# NSSTC-BAK.net
KiCad netlist of a schematic drawn in Altium Designer
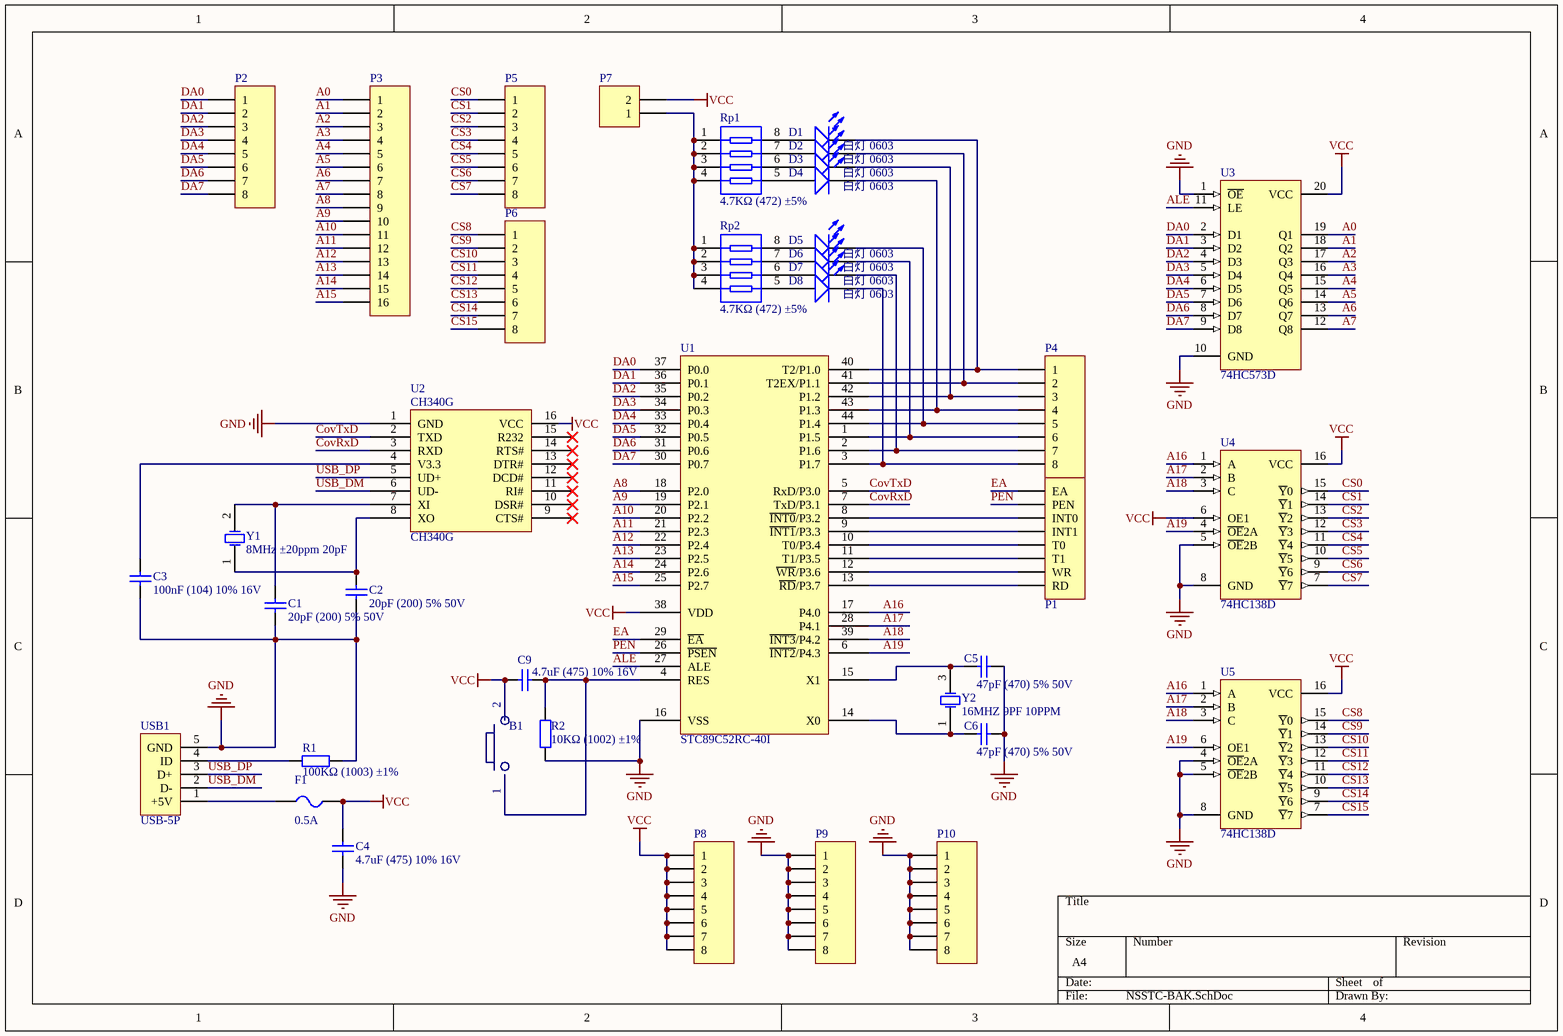
[diagram p0: NSSTC-BAK.SchDoc]

(export (version "E")
  (design (tool "Eeschema 10.0.6"))
  (components
    (comp (ref "B1")
      (value "B?")
      (footprint "MetalButton")
      (libsource (lib "MetalButton") (part "MetalButton"))
    )
    (comp (ref "C1")
      (value "20pF (200) 5% 50V")
      (footprint "0402_C")
      (description "贴片电容")
      (libsource (lib "Miscellaneous Devices LC") (part "0402 20pF (200) 5% 50V"))
    )
    (comp (ref "C2")
      (value "20pF (200) 5% 50V")
      (footprint "0402_C")
      (description "贴片电容")
      (libsource (lib "Miscellaneous Devices LC") (part "0402 20pF (200) 5% 50V"))
    )
    (comp (ref "C3")
      (value "100nF (104) 10% 16V")
      (footprint "0402_C")
      (description "贴片电容")
      (libsource (lib "Miscellaneous Devices LC") (part "0402 100nF (104) 10% 16V"))
    )
    (comp (ref "C4")
      (value "4.7uF (475) 10% 16V")
      (footprint "0603_C")
      (description "贴片电容")
      (libsource (lib "Miscellaneous Devices LC") (part "0603 4.7uF (475) 10% 16V"))
    )
    (comp (ref "C5")
      (value "47pF (470) 5% 50V")
      (footprint "0402_C")
      (description "贴片电容")
      (libsource (lib "Miscellaneous Devices LC") (part "0402 47pF (470) 5% 50V"))
    )
    (comp (ref "C6")
      (value "47pF (470) 5% 50V")
      (footprint "0402_C")
      (description "贴片电容")
      (libsource (lib "Miscellaneous Devices LC") (part "0402 47pF (470) 5% 50V"))
    )
    (comp (ref "C9")
      (value "4.7uF (475) 10% 16V")
      (footprint "0603_C")
      (description "贴片电容")
      (libsource (lib "Miscellaneous Devices LC") (part "0603 4.7uF (475) 10% 16V"))
    )
    (comp (ref "D1")
      (value "白灯 0603")
      (footprint "0603_LED_S1")
      (description "发光二极管")
      (libsource (lib "Miscellaneous Devices LC") (part "0603 白灯"))
    )
    (comp (ref "D2")
      (value "白灯 0603")
      (footprint "0603_LED_S1")
      (description "发光二极管")
      (libsource (lib "Miscellaneous Devices LC") (part "0603 白灯"))
    )
    (comp (ref "D3")
      (value "白灯 0603")
      (footprint "0603_LED_S1")
      (description "发光二极管")
      (libsource (lib "Miscellaneous Devices LC") (part "0603 白灯"))
    )
    (comp (ref "D4")
      (value "白灯 0603")
      (footprint "0603_LED_S1")
      (description "发光二极管")
      (libsource (lib "Miscellaneous Devices LC") (part "0603 白灯"))
    )
    (comp (ref "D5")
      (value "白灯 0603")
      (footprint "0603_LED_S1")
      (description "发光二极管")
      (libsource (lib "Miscellaneous Devices LC") (part "0603 白灯"))
    )
    (comp (ref "D6")
      (value "白灯 0603")
      (footprint "0603_LED_S1")
      (description "发光二极管")
      (libsource (lib "Miscellaneous Devices LC") (part "0603 白灯"))
    )
    (comp (ref "D7")
      (value "白灯 0603")
      (footprint "0603_LED_S1")
      (description "发光二极管")
      (libsource (lib "Miscellaneous Devices LC") (part "0603 白灯"))
    )
    (comp (ref "D8")
      (value "白灯 0603")
      (footprint "0603_LED_S1")
      (description "发光二极管")
      (libsource (lib "Miscellaneous Devices LC") (part "0603 白灯"))
    )
    (comp (ref "F1")
      (value "0.5A")
      (footprint "FU 0603")
      (description "贴片保险丝")
      (fields (field (name "版权归属") "源创客"))
      (libsource (lib "10.1 - 保险丝-晶振") (part "FU"))
    )
    (comp (ref "P1")
      (value "Header 8")
      (footprint "HDR1X8")
      (description "Header, 8-Pin")
      (fields (field (name "PUBLISHER") "Altium Limited"))
      (libsource (lib "Miscellaneous Connectors") (part "Header 8"))
    )
    (comp (ref "P2")
      (value "Header 8")
      (footprint "HDR1X8")
      (description "Header, 8-Pin")
      (fields (field (name "PUBLISHER") "Altium Limited"))
      (libsource (lib "Miscellaneous Connectors") (part "Header 8"))
    )
    (comp (ref "P3")
      (value "Header 16")
      (footprint "HDR1X16")
      (description "Header, 16-Pin")
      (fields (field (name "PUBLISHER") "Altium Limited"))
      (libsource (lib "Miscellaneous Connectors") (part "Header 16"))
    )
    (comp (ref "P4")
      (value "Header 8")
      (footprint "HDR1X8")
      (description "Header, 8-Pin")
      (fields (field (name "PUBLISHER") "Altium Limited"))
      (libsource (lib "Miscellaneous Connectors") (part "Header 8"))
    )
    (comp (ref "P5")
      (value "Header 8")
      (footprint "HDR1X8")
      (description "Header, 8-Pin")
      (fields (field (name "PUBLISHER") "Altium Limited"))
      (libsource (lib "Miscellaneous Connectors") (part "Header 8"))
    )
    (comp (ref "P6")
      (value "Header 8")
      (footprint "HDR1X8")
      (description "Header, 8-Pin")
      (fields (field (name "PUBLISHER") "Altium Limited"))
      (libsource (lib "Miscellaneous Connectors") (part "Header 8"))
    )
    (comp (ref "P7")
      (value "Header 2")
      (footprint "HDR1X2")
      (description "Header, 2-Pin")
      (fields (field (name "PUBLISHER") "Altium Limited"))
      (libsource (lib "Miscellaneous Connectors") (part "Header 2"))
    )
    (comp (ref "P8")
      (value "Header 8")
      (footprint "HDR1X8")
      (description "Header, 8-Pin")
      (fields (field (name "PUBLISHER") "Altium Limited"))
      (libsource (lib "Miscellaneous Connectors") (part "Header 8"))
    )
    (comp (ref "P9")
      (value "Header 8")
      (footprint "HDR1X8")
      (description "Header, 8-Pin")
      (fields (field (name "PUBLISHER") "Altium Limited"))
      (libsource (lib "Miscellaneous Connectors") (part "Header 8"))
    )
    (comp (ref "P10")
      (value "Header 8")
      (footprint "HDR1X8")
      (description "Header, 8-Pin")
      (fields (field (name "PUBLISHER") "Altium Limited"))
      (libsource (lib "Miscellaneous Connectors") (part "Header 8"))
    )
    (comp (ref "R1")
      (value "100KΩ (1003) ±1%")
      (footprint "0402_R")
      (description "贴片电阻")
      (libsource (lib "Miscellaneous Devices LC") (part "0402 100KΩ (1003) 1%"))
    )
    (comp (ref "R2")
      (value "10KΩ (1002) ±1%")
      (footprint "0402_R")
      (description "贴片电阻")
      (libsource (lib "Miscellaneous Devices LC") (part "0402 10KΩ (1002) 1%"))
    )
    (comp (ref "Rp1")
      (value "4.7KΩ (472) ±5%")
      (footprint "0603_Rx4")
      (description "贴片排阻")
      (libsource (lib "Miscellaneous Devices LC") (part "0603*4  4.7KΩ (472) 5%"))
    )
    (comp (ref "Rp2")
      (value "4.7KΩ (472) ±5%")
      (footprint "0603_Rx4")
      (description "贴片排阻")
      (libsource (lib "Miscellaneous Devices LC") (part "0603*4  4.7KΩ (472) 5%"))
    )
    (comp (ref "U1")
      (value "STC89C52RC-40I")
      (footprint "LQFP-44_10x10x08P")
      (description "MCU")
      (libsource (lib "Miscellaneous Devices LC") (part "STC89C52RC-40I"))
    )
    (comp (ref "U2")
      (value "CH340G")
      (footprint "SOIC-16_150mil")
      (description "USB")
      (libsource (lib "Miscellaneous Devices LC") (part "CH340G_[C14267]"))
    )
    (comp (ref "U3")
      (value "74HC573D")
      (footprint "SOIC-20_300mil")
      (description "74系列逻辑芯片")
      (libsource (lib "Miscellaneous Devices LC") (part "74HC573D_[C5608]"))
    )
    (comp (ref "U4")
      (value "74HC138D")
      (footprint "SOIC-16_150mil")
      (description "74系列逻辑芯片")
      (libsource (lib "Miscellaneous Devices LC") (part "74HC138D_[C5602]"))
    )
    (comp (ref "U5")
      (value "74HC138D")
      (footprint "SOIC-16_150mil")
      (description "74系列逻辑芯片")
      (libsource (lib "Miscellaneous Devices LC") (part "74HC138D_[C5602]"))
    )
    (comp (ref "USB1")
      (value "USB-5P")
      (footprint "USB-MICRO_D")
      (description "微型USB母座")
      (fields (field (name "版权归属") "源创客"))
      (libsource (lib "4.1   - 接口类") (part "USB-5P"))
    )
    (comp (ref "Y1")
      (value "8MHz ±20ppm 20pF")
      (footprint "SMD-5032_2P")
      (description "贴片晶振")
      (libsource (lib "Miscellaneous Devices LC") (part "SMD-5032_2P 8MHz 20ppm 20pF"))
    )
    (comp (ref "Y2")
      (value "16MHZ 9PF 10PPM")
      (footprint "SMD-3225_4P")
      (description "贴片晶振")
      (libsource (lib "Miscellaneous Devices LC") (part "SMD-3225_4P  16MHZ 9PF 10PPM"))
    )
  )
  (nets
    (net (code "1") (name "/A0") (class "Default")
      (node (ref "P3") (pin "1") (pinfunction "1_1") (pintype "passive"))
      (node (ref "U3") (pin "19") (pinfunction "Q1_19") (pintype "tri_state"))
    )
    (net (code "2") (name "/A1") (class "Default")
      (node (ref "P3") (pin "2") (pinfunction "2_2") (pintype "passive"))
      (node (ref "U3") (pin "18") (pinfunction "Q2_18") (pintype "tri_state"))
    )
    (net (code "3") (name "/A2") (class "Default")
      (node (ref "P3") (pin "3") (pinfunction "3_3") (pintype "passive"))
      (node (ref "U3") (pin "17") (pinfunction "Q3_17") (pintype "tri_state"))
    )
    (net (code "4") (name "/A3") (class "Default")
      (node (ref "P3") (pin "4") (pinfunction "4_4") (pintype "passive"))
      (node (ref "U3") (pin "16") (pinfunction "Q4_16") (pintype "tri_state"))
    )
    (net (code "5") (name "/A4") (class "Default")
      (node (ref "P3") (pin "5") (pinfunction "5_5") (pintype "passive"))
      (node (ref "U3") (pin "15") (pinfunction "Q5_15") (pintype "tri_state"))
    )
    (net (code "6") (name "/A5") (class "Default")
      (node (ref "P3") (pin "6") (pinfunction "6_6") (pintype "passive"))
      (node (ref "U3") (pin "14") (pinfunction "Q6_14") (pintype "tri_state"))
    )
    (net (code "7") (name "/A6") (class "Default")
      (node (ref "P3") (pin "7") (pinfunction "7_7") (pintype "passive"))
      (node (ref "U3") (pin "13") (pinfunction "Q7_13") (pintype "tri_state"))
    )
    (net (code "8") (name "/A7") (class "Default")
      (node (ref "P3") (pin "8") (pinfunction "8_8") (pintype "passive"))
      (node (ref "U3") (pin "12") (pinfunction "Q8_12") (pintype "tri_state"))
    )
    (net (code "9") (name "/A8") (class "Default")
      (node (ref "P3") (pin "9") (pinfunction "9_9") (pintype "passive"))
      (node (ref "U1") (pin "18") (pinfunction "P2.0_18") (pintype "passive"))
    )
    (net (code "10") (name "/A9") (class "Default")
      (node (ref "P3") (pin "10") (pinfunction "10_10") (pintype "passive"))
      (node (ref "U1") (pin "19") (pinfunction "P2.1_19") (pintype "passive"))
    )
    (net (code "11") (name "/A10") (class "Default")
      (node (ref "P3") (pin "11") (pinfunction "11_11") (pintype "passive"))
      (node (ref "U1") (pin "20") (pinfunction "P2.2_20") (pintype "passive"))
    )
    (net (code "12") (name "/A11") (class "Default")
      (node (ref "P3") (pin "12") (pinfunction "12_12") (pintype "passive"))
      (node (ref "U1") (pin "21") (pinfunction "P2.3_21") (pintype "passive"))
    )
    (net (code "13") (name "/A12") (class "Default")
      (node (ref "P3") (pin "13") (pinfunction "13_13") (pintype "passive"))
      (node (ref "U1") (pin "22") (pinfunction "P2.4_22") (pintype "passive"))
    )
    (net (code "14") (name "/A13") (class "Default")
      (node (ref "P3") (pin "14") (pinfunction "14_14") (pintype "passive"))
      (node (ref "U1") (pin "23") (pinfunction "P2.5_23") (pintype "passive"))
    )
    (net (code "15") (name "/A14") (class "Default")
      (node (ref "P3") (pin "15") (pinfunction "15_15") (pintype "passive"))
      (node (ref "U1") (pin "24") (pinfunction "P2.6_24") (pintype "passive"))
    )
    (net (code "16") (name "/A15") (class "Default")
      (node (ref "P3") (pin "16") (pinfunction "16_16") (pintype "passive"))
      (node (ref "U1") (pin "25") (pinfunction "P2.7_25") (pintype "passive"))
    )
    (net (code "17") (name "/A16") (class "Default")
      (node (ref "U1") (pin "17") (pinfunction "P4.0_17") (pintype "passive"))
      (node (ref "U4") (pin "1") (pinfunction "A_1") (pintype "input"))
      (node (ref "U5") (pin "1") (pinfunction "A_1") (pintype "input"))
    )
    (net (code "18") (name "/A17") (class "Default")
      (node (ref "U1") (pin "28") (pinfunction "P4.1_28") (pintype "passive"))
      (node (ref "U4") (pin "2") (pinfunction "B_2") (pintype "input"))
      (node (ref "U5") (pin "2") (pinfunction "B_2") (pintype "input"))
    )
    (net (code "19") (name "/A18") (class "Default")
      (node (ref "U1") (pin "39") (pinfunction "~{INT3}/P4.2_39") (pintype "passive"))
      (node (ref "U4") (pin "3") (pinfunction "C_3") (pintype "input"))
      (node (ref "U5") (pin "3") (pinfunction "C_3") (pintype "input"))
    )
    (net (code "20") (name "/A19") (class "Default")
      (node (ref "U1") (pin "6") (pinfunction "~{INT2}/P4.3_6") (pintype "passive"))
      (node (ref "U4") (pin "4") (pinfunction "~{OE}2A_4") (pintype "input"))
      (node (ref "U5") (pin "6") (pinfunction "OE1_6") (pintype "input"))
    )
    (net (code "21") (name "/ALE") (class "Default")
      (node (ref "U1") (pin "27") (pinfunction "ALE_27") (pintype "passive"))
      (node (ref "U3") (pin "11") (pinfunction "LE_11") (pintype "input"))
    )
    (net (code "22") (name "/CS0") (class "Default")
      (node (ref "P5") (pin "1") (pinfunction "1_1") (pintype "passive"))
      (node (ref "U4") (pin "15") (pinfunction "~{Y}0_15") (pintype "output"))
    )
    (net (code "23") (name "/CS1") (class "Default")
      (node (ref "P5") (pin "2") (pinfunction "2_2") (pintype "passive"))
      (node (ref "U4") (pin "14") (pinfunction "~{Y}1_14") (pintype "output"))
    )
    (net (code "24") (name "/CS2") (class "Default")
      (node (ref "P5") (pin "3") (pinfunction "3_3") (pintype "passive"))
      (node (ref "U4") (pin "13") (pinfunction "~{Y}2_13") (pintype "output"))
    )
    (net (code "25") (name "/CS3") (class "Default")
      (node (ref "P5") (pin "4") (pinfunction "4_4") (pintype "passive"))
      (node (ref "U4") (pin "12") (pinfunction "~{Y}3_12") (pintype "output"))
    )
    (net (code "26") (name "/CS4") (class "Default")
      (node (ref "P5") (pin "5") (pinfunction "5_5") (pintype "passive"))
      (node (ref "U4") (pin "11") (pinfunction "~{Y}4_11") (pintype "output"))
    )
    (net (code "27") (name "/CS5") (class "Default")
      (node (ref "P5") (pin "6") (pinfunction "6_6") (pintype "passive"))
      (node (ref "U4") (pin "10") (pinfunction "~{Y}5_10") (pintype "output"))
    )
    (net (code "28") (name "/CS6") (class "Default")
      (node (ref "P5") (pin "7") (pinfunction "7_7") (pintype "passive"))
      (node (ref "U4") (pin "9") (pinfunction "~{Y}6_9") (pintype "output"))
    )
    (net (code "29") (name "/CS7") (class "Default")
      (node (ref "P5") (pin "8") (pinfunction "8_8") (pintype "passive"))
      (node (ref "U4") (pin "7") (pinfunction "~{Y}7_7") (pintype "output"))
    )
    (net (code "30") (name "/CS8") (class "Default")
      (node (ref "P6") (pin "1") (pinfunction "1_1") (pintype "passive"))
      (node (ref "U5") (pin "15") (pinfunction "~{Y}0_15") (pintype "output"))
    )
    (net (code "31") (name "/CS9") (class "Default")
      (node (ref "P6") (pin "2") (pinfunction "2_2") (pintype "passive"))
      (node (ref "U5") (pin "14") (pinfunction "~{Y}1_14") (pintype "output"))
    )
    (net (code "32") (name "/CS10") (class "Default")
      (node (ref "P6") (pin "3") (pinfunction "3_3") (pintype "passive"))
      (node (ref "U5") (pin "13") (pinfunction "~{Y}2_13") (pintype "output"))
    )
    (net (code "33") (name "/CS11") (class "Default")
      (node (ref "P6") (pin "4") (pinfunction "4_4") (pintype "passive"))
      (node (ref "U5") (pin "12") (pinfunction "~{Y}3_12") (pintype "output"))
    )
    (net (code "34") (name "/CS12") (class "Default")
      (node (ref "P6") (pin "5") (pinfunction "5_5") (pintype "passive"))
      (node (ref "U5") (pin "11") (pinfunction "~{Y}4_11") (pintype "output"))
    )
    (net (code "35") (name "/CS13") (class "Default")
      (node (ref "P6") (pin "6") (pinfunction "6_6") (pintype "passive"))
      (node (ref "U5") (pin "10") (pinfunction "~{Y}5_10") (pintype "output"))
    )
    (net (code "36") (name "/CS14") (class "Default")
      (node (ref "P6") (pin "7") (pinfunction "7_7") (pintype "passive"))
      (node (ref "U5") (pin "9") (pinfunction "~{Y}6_9") (pintype "output"))
    )
    (net (code "37") (name "/CS15") (class "Default")
      (node (ref "P6") (pin "8") (pinfunction "8_8") (pintype "passive"))
      (node (ref "U5") (pin "7") (pinfunction "~{Y}7_7") (pintype "output"))
    )
    (net (code "38") (name "/CovRxD") (class "Default")
      (node (ref "U1") (pin "7") (pinfunction "TxD/P3.1_7") (pintype "passive"))
      (node (ref "U2") (pin "3") (pinfunction "RXD_3") (pintype "passive"))
    )
    (net (code "39") (name "/CovTxD") (class "Default")
      (node (ref "U1") (pin "5") (pinfunction "RxD/P3.0_5") (pintype "passive"))
      (node (ref "U2") (pin "2") (pinfunction "TXD_2") (pintype "passive"))
    )
    (net (code "40") (name "/DA0") (class "Default")
      (node (ref "P2") (pin "1") (pinfunction "1_1") (pintype "passive"))
      (node (ref "U1") (pin "37") (pinfunction "P0.0_37") (pintype "passive"))
      (node (ref "U3") (pin "2") (pinfunction "D1_2") (pintype "input"))
    )
    (net (code "41") (name "/DA1") (class "Default")
      (node (ref "P2") (pin "2") (pinfunction "2_2") (pintype "passive"))
      (node (ref "U1") (pin "36") (pinfunction "P0.1_36") (pintype "passive"))
      (node (ref "U3") (pin "3") (pinfunction "D2_3") (pintype "input"))
    )
    (net (code "42") (name "/DA2") (class "Default")
      (node (ref "P2") (pin "3") (pinfunction "3_3") (pintype "passive"))
      (node (ref "U1") (pin "35") (pinfunction "P0.2_35") (pintype "passive"))
      (node (ref "U3") (pin "4") (pinfunction "D3_4") (pintype "input"))
    )
    (net (code "43") (name "/DA3") (class "Default")
      (node (ref "P2") (pin "4") (pinfunction "4_4") (pintype "passive"))
      (node (ref "U1") (pin "34") (pinfunction "P0.3_34") (pintype "passive"))
      (node (ref "U3") (pin "5") (pinfunction "D4_5") (pintype "input"))
    )
    (net (code "44") (name "/DA4") (class "Default")
      (node (ref "P2") (pin "5") (pinfunction "5_5") (pintype "passive"))
      (node (ref "U1") (pin "33") (pinfunction "P0.4_33") (pintype "passive"))
      (node (ref "U3") (pin "6") (pinfunction "D5_6") (pintype "input"))
    )
    (net (code "45") (name "/DA5") (class "Default")
      (node (ref "P2") (pin "6") (pinfunction "6_6") (pintype "passive"))
      (node (ref "U1") (pin "32") (pinfunction "P0.5_32") (pintype "passive"))
      (node (ref "U3") (pin "7") (pinfunction "D6_7") (pintype "input"))
    )
    (net (code "46") (name "/DA6") (class "Default")
      (node (ref "P2") (pin "7") (pinfunction "7_7") (pintype "passive"))
      (node (ref "U1") (pin "31") (pinfunction "P0.6_31") (pintype "passive"))
      (node (ref "U3") (pin "8") (pinfunction "D7_8") (pintype "input"))
    )
    (net (code "47") (name "/DA7") (class "Default")
      (node (ref "P2") (pin "8") (pinfunction "8_8") (pintype "passive"))
      (node (ref "U1") (pin "30") (pinfunction "P0.7_30") (pintype "passive"))
      (node (ref "U3") (pin "9") (pinfunction "D8_9") (pintype "input"))
    )
    (net (code "48") (name "/EA") (class "Default")
      (node (ref "P1") (pin "1") (pinfunction "1_1") (pintype "passive"))
      (node (ref "U1") (pin "29") (pinfunction "~{EA}_29") (pintype "passive"))
    )
    (net (code "49") (name "/PEN") (class "Default")
      (node (ref "P1") (pin "2") (pinfunction "2_2") (pintype "passive"))
      (node (ref "U1") (pin "26") (pinfunction "~{PSEN}_26") (pintype "passive"))
    )
    (net (code "50") (name "/USB_DM") (class "Default")
      (node (ref "U2") (pin "6") (pinfunction "UD-_6") (pintype "passive"))
      (node (ref "USB1") (pin "2") (pinfunction "D-_2") (pintype "passive"))
    )
    (net (code "51") (name "/USB_DP") (class "Default")
      (node (ref "U2") (pin "5") (pinfunction "UD+_5") (pintype "passive"))
      (node (ref "USB1") (pin "3") (pinfunction "D+_3") (pintype "passive"))
    )
    (net (code "52") (name "GND") (class "Default")
      (node (ref "C1") (pin "1") (pinfunction "1_1") (pintype "passive"))
      (node (ref "C2") (pin "1") (pinfunction "1_1") (pintype "passive"))
      (node (ref "C3") (pin "1") (pinfunction "1_1") (pintype "passive"))
      (node (ref "C4") (pin "1") (pinfunction "1_1") (pintype "passive"))
      (node (ref "C5") (pin "2") (pinfunction "2_2") (pintype "passive"))
      (node (ref "C6") (pin "2") (pinfunction "2_2") (pintype "passive"))
      (node (ref "P10") (pin "1") (pinfunction "1_1") (pintype "passive"))
      (node (ref "P10") (pin "2") (pinfunction "2_2") (pintype "passive"))
      (node (ref "P10") (pin "3") (pinfunction "3_3") (pintype "passive"))
      (node (ref "P10") (pin "4") (pinfunction "4_4") (pintype "passive"))
      (node (ref "P10") (pin "5") (pinfunction "5_5") (pintype "passive"))
      (node (ref "P10") (pin "6") (pinfunction "6_6") (pintype "passive"))
      (node (ref "P10") (pin "7") (pinfunction "7_7") (pintype "passive"))
      (node (ref "P10") (pin "8") (pinfunction "8_8") (pintype "passive"))
      (node (ref "P9") (pin "1") (pinfunction "1_1") (pintype "passive"))
      (node (ref "P9") (pin "2") (pinfunction "2_2") (pintype "passive"))
      (node (ref "P9") (pin "3") (pinfunction "3_3") (pintype "passive"))
      (node (ref "P9") (pin "4") (pinfunction "4_4") (pintype "passive"))
      (node (ref "P9") (pin "5") (pinfunction "5_5") (pintype "passive"))
      (node (ref "P9") (pin "6") (pinfunction "6_6") (pintype "passive"))
      (node (ref "P9") (pin "7") (pinfunction "7_7") (pintype "passive"))
      (node (ref "P9") (pin "8") (pinfunction "8_8") (pintype "passive"))
      (node (ref "R1") (pin "2") (pinfunction "2_2") (pintype "passive"))
      (node (ref "R2") (pin "1") (pinfunction "1_1") (pintype "passive"))
      (node (ref "U1") (pin "16") (pinfunction "VSS_16") (pintype "passive"))
      (node (ref "U2") (pin "1") (pinfunction "GND_1") (pintype "passive"))
      (node (ref "U3") (pin "1") (pinfunction "~{OE}_1") (pintype "input"))
      (node (ref "U3") (pin "10") (pinfunction "GND_10") (pintype "power_in"))
      (node (ref "U4") (pin "5") (pinfunction "~{OE}2B_5") (pintype "input"))
      (node (ref "U4") (pin "8") (pinfunction "GND_8") (pintype "power_in"))
      (node (ref "U5") (pin "4") (pinfunction "~{OE}2A_4") (pintype "input"))
      (node (ref "U5") (pin "5") (pinfunction "~{OE}2B_5") (pintype "input"))
      (node (ref "U5") (pin "8") (pinfunction "GND_8") (pintype "power_in"))
      (node (ref "USB1") (pin "5") (pinfunction "GND_5") (pintype "passive"))
    )
    (net (code "53") (name "Net-(D1-PadA)") (class "Default")
      (node (ref "D1") (pin "A") (pinfunction "A_A") (pintype "passive"))
      (node (ref "Rp1") (pin "8") (pinfunction "8_8") (pintype "passive"))
    )
    (net (code "54") (name "Net-(D2-PadA)") (class "Default")
      (node (ref "D2") (pin "A") (pinfunction "A_A") (pintype "passive"))
      (node (ref "Rp1") (pin "7") (pinfunction "7_7") (pintype "passive"))
    )
    (net (code "55") (name "Net-(D3-PadA)") (class "Default")
      (node (ref "D3") (pin "A") (pinfunction "A_A") (pintype "passive"))
      (node (ref "Rp1") (pin "6") (pinfunction "6_6") (pintype "passive"))
    )
    (net (code "56") (name "Net-(D4-PadA)") (class "Default")
      (node (ref "D4") (pin "A") (pinfunction "A_A") (pintype "passive"))
      (node (ref "Rp1") (pin "5") (pinfunction "5_5") (pintype "passive"))
    )
    (net (code "57") (name "Net-(D5-PadA)") (class "Default")
      (node (ref "D5") (pin "A") (pinfunction "A_A") (pintype "passive"))
      (node (ref "Rp2") (pin "8") (pinfunction "8_8") (pintype "passive"))
    )
    (net (code "58") (name "Net-(D6-PadA)") (class "Default")
      (node (ref "D6") (pin "A") (pinfunction "A_A") (pintype "passive"))
      (node (ref "Rp2") (pin "7") (pinfunction "7_7") (pintype "passive"))
    )
    (net (code "59") (name "Net-(D7-PadA)") (class "Default")
      (node (ref "D7") (pin "A") (pinfunction "A_A") (pintype "passive"))
      (node (ref "Rp2") (pin "6") (pinfunction "6_6") (pintype "passive"))
    )
    (net (code "60") (name "Net-(D8-PadA)") (class "Default")
      (node (ref "D8") (pin "A") (pinfunction "A_A") (pintype "passive"))
      (node (ref "Rp2") (pin "5") (pinfunction "5_5") (pintype "passive"))
    )
    (net (code "61") (name "Net-(P7-Pad1)") (class "Default")
      (node (ref "P7") (pin "1") (pinfunction "1_1") (pintype "passive"))
      (node (ref "Rp1") (pin "1") (pinfunction "1_1") (pintype "passive"))
      (node (ref "Rp1") (pin "2") (pinfunction "2_2") (pintype "passive"))
      (node (ref "Rp1") (pin "3") (pinfunction "3_3") (pintype "passive"))
      (node (ref "Rp1") (pin "4") (pinfunction "4_4") (pintype "passive"))
      (node (ref "Rp2") (pin "1") (pinfunction "1_1") (pintype "passive"))
      (node (ref "Rp2") (pin "2") (pinfunction "2_2") (pintype "passive"))
      (node (ref "Rp2") (pin "3") (pinfunction "3_3") (pintype "passive"))
      (node (ref "Rp2") (pin "4") (pinfunction "4_4") (pintype "passive"))
    )
    (net (code "62") (name "Net-(U1-P1.2)") (class "Default")
      (node (ref "D3") (pin "K") (pinfunction "K_K") (pintype "passive"))
      (node (ref "P4") (pin "3") (pinfunction "3_3") (pintype "passive"))
      (node (ref "U1") (pin "42") (pinfunction "P1.2_42") (pintype "passive"))
    )
    (net (code "63") (name "Net-(U1-P1.3)") (class "Default")
      (node (ref "D4") (pin "K") (pinfunction "K_K") (pintype "passive"))
      (node (ref "P4") (pin "4") (pinfunction "4_4") (pintype "passive"))
      (node (ref "U1") (pin "43") (pinfunction "P1.3_43") (pintype "passive"))
    )
    (net (code "64") (name "Net-(U1-P1.4)") (class "Default")
      (node (ref "D5") (pin "K") (pinfunction "K_K") (pintype "passive"))
      (node (ref "P4") (pin "5") (pinfunction "5_5") (pintype "passive"))
      (node (ref "U1") (pin "44") (pinfunction "P1.4_44") (pintype "passive"))
    )
    (net (code "65") (name "Net-(U1-P1.5)") (class "Default")
      (node (ref "D6") (pin "K") (pinfunction "K_K") (pintype "passive"))
      (node (ref "P4") (pin "6") (pinfunction "6_6") (pintype "passive"))
      (node (ref "U1") (pin "1") (pinfunction "P1.5_1") (pintype "passive"))
    )
    (net (code "66") (name "Net-(U1-P1.6)") (class "Default")
      (node (ref "D7") (pin "K") (pinfunction "K_K") (pintype "passive"))
      (node (ref "P4") (pin "7") (pinfunction "7_7") (pintype "passive"))
      (node (ref "U1") (pin "2") (pinfunction "P1.6_2") (pintype "passive"))
    )
    (net (code "67") (name "Net-(U1-P1.7)") (class "Default")
      (node (ref "D8") (pin "K") (pinfunction "K_K") (pintype "passive"))
      (node (ref "P4") (pin "8") (pinfunction "8_8") (pintype "passive"))
      (node (ref "U1") (pin "3") (pinfunction "P1.7_3") (pintype "passive"))
    )
    (net (code "68") (name "Net-(U1-RES)") (class "Default")
      (node (ref "B1") (pin "1") (pinfunction "1_1") (pintype "passive"))
      (node (ref "C9") (pin "1") (pinfunction "1_1") (pintype "passive"))
      (node (ref "R2") (pin "2") (pinfunction "2_2") (pintype "passive"))
      (node (ref "U1") (pin "4") (pinfunction "RES_4") (pintype "passive"))
    )
    (net (code "69") (name "Net-(U1-T0{slash}P3.4)") (class "Default")
      (node (ref "P1") (pin "5") (pinfunction "5_5") (pintype "passive"))
      (node (ref "U1") (pin "10") (pinfunction "T0/P3.4_10") (pintype "passive"))
    )
    (net (code "70") (name "Net-(U1-T1{slash}P3.5)") (class "Default")
      (node (ref "P1") (pin "6") (pinfunction "6_6") (pintype "passive"))
      (node (ref "U1") (pin "11") (pinfunction "T1/P3.5_11") (pintype "passive"))
    )
    (net (code "71") (name "Net-(U1-T2EX{slash}P1.1)") (class "Default")
      (node (ref "D2") (pin "K") (pinfunction "K_K") (pintype "passive"))
      (node (ref "P4") (pin "2") (pinfunction "2_2") (pintype "passive"))
      (node (ref "U1") (pin "41") (pinfunction "T2EX/P1.1_41") (pintype "passive"))
    )
    (net (code "72") (name "Net-(U1-T2{slash}P1.0)") (class "Default")
      (node (ref "D1") (pin "K") (pinfunction "K_K") (pintype "passive"))
      (node (ref "P4") (pin "1") (pinfunction "1_1") (pintype "passive"))
      (node (ref "U1") (pin "40") (pinfunction "T2/P1.0_40") (pintype "passive"))
    )
    (net (code "73") (name "Net-(U1-X0)") (class "Default")
      (node (ref "C6") (pin "1") (pinfunction "1_1") (pintype "passive"))
      (node (ref "U1") (pin "14") (pinfunction "X0_14") (pintype "passive"))
      (node (ref "Y2") (pin "1") (pinfunction "OSC1_1") (pintype "passive"))
    )
    (net (code "74") (name "Net-(U1-X1)") (class "Default")
      (node (ref "C5") (pin "1") (pinfunction "1_1") (pintype "passive"))
      (node (ref "U1") (pin "15") (pinfunction "X1_15") (pintype "passive"))
      (node (ref "Y2") (pin "3") (pinfunction "OSC2_3") (pintype "passive"))
    )
    (net (code "75") (name "Net-(U1-~{INT0}{slash}P3.2)") (class "Default")
      (node (ref "P1") (pin "3") (pinfunction "3_3") (pintype "passive"))
      (node (ref "U1") (pin "8") (pinfunction "~{INT0}/P3.2_8") (pintype "passive"))
    )
    (net (code "76") (name "Net-(U1-~{INT1}{slash}P3.3)") (class "Default")
      (node (ref "P1") (pin "4") (pinfunction "4_4") (pintype "passive"))
      (node (ref "U1") (pin "9") (pinfunction "~{INT1}/P3.3_9") (pintype "passive"))
    )
    (net (code "77") (name "Net-(U1-~{RD}{slash}P3.7)") (class "Default")
      (node (ref "P1") (pin "8") (pinfunction "8_8") (pintype "passive"))
      (node (ref "U1") (pin "13") (pinfunction "~{RD}/P3.7_13") (pintype "passive"))
    )
    (net (code "78") (name "Net-(U1-~{WR}{slash}P3.6)") (class "Default")
      (node (ref "P1") (pin "7") (pinfunction "7_7") (pintype "passive"))
      (node (ref "U1") (pin "12") (pinfunction "~{WR}/P3.6_12") (pintype "passive"))
    )
    (net (code "79") (name "Net-(U2-V3.3)") (class "Default")
      (node (ref "C3") (pin "2") (pinfunction "2_2") (pintype "passive"))
      (node (ref "U2") (pin "4") (pinfunction "V3.3_4") (pintype "passive"))
    )
    (net (code "80") (name "Net-(U2-XI)") (class "Default")
      (node (ref "C1") (pin "2") (pinfunction "2_2") (pintype "passive"))
      (node (ref "U2") (pin "7") (pinfunction "XI_7") (pintype "passive"))
      (node (ref "Y1") (pin "2") (pinfunction "OSC2_2") (pintype "passive"))
    )
    (net (code "81") (name "Net-(U2-XO)") (class "Default")
      (node (ref "C2") (pin "2") (pinfunction "2_2") (pintype "passive"))
      (node (ref "U2") (pin "8") (pinfunction "XO_8") (pintype "passive"))
      (node (ref "Y1") (pin "1") (pinfunction "OSC1_1") (pintype "passive"))
    )
    (net (code "82") (name "Net-(USB1-+5V)") (class "Default")
      (node (ref "F1") (pin "2") (pinfunction "2_2") (pintype "passive"))
      (node (ref "USB1") (pin "1") (pinfunction "+5V_1") (pintype "passive"))
    )
    (net (code "83") (name "Net-(USB1-ID)") (class "Default")
      (node (ref "R1") (pin "1") (pinfunction "1_1") (pintype "passive"))
      (node (ref "USB1") (pin "4") (pinfunction "ID_4") (pintype "passive"))
    )
    (net (code "84") (name "VCC") (class "Default")
      (node (ref "B1") (pin "2") (pinfunction "2_2") (pintype "passive"))
      (node (ref "C4") (pin "2") (pinfunction "2_2") (pintype "passive"))
      (node (ref "C9") (pin "2") (pinfunction "2_2") (pintype "passive"))
      (node (ref "F1") (pin "1") (pinfunction "1_1") (pintype "passive"))
      (node (ref "P7") (pin "2") (pinfunction "2_2") (pintype "passive"))
      (node (ref "P8") (pin "1") (pinfunction "1_1") (pintype "passive"))
      (node (ref "P8") (pin "2") (pinfunction "2_2") (pintype "passive"))
      (node (ref "P8") (pin "3") (pinfunction "3_3") (pintype "passive"))
      (node (ref "P8") (pin "4") (pinfunction "4_4") (pintype "passive"))
      (node (ref "P8") (pin "5") (pinfunction "5_5") (pintype "passive"))
      (node (ref "P8") (pin "6") (pinfunction "6_6") (pintype "passive"))
      (node (ref "P8") (pin "7") (pinfunction "7_7") (pintype "passive"))
      (node (ref "P8") (pin "8") (pinfunction "8_8") (pintype "passive"))
      (node (ref "U1") (pin "38") (pinfunction "VDD_38") (pintype "passive"))
      (node (ref "U2") (pin "16") (pinfunction "VCC_16") (pintype "passive"))
      (node (ref "U3") (pin "20") (pinfunction "VCC_20") (pintype "power_in"))
      (node (ref "U4") (pin "16") (pinfunction "VCC_16") (pintype "power_in"))
      (node (ref "U4") (pin "6") (pinfunction "OE1_6") (pintype "input"))
      (node (ref "U5") (pin "16") (pinfunction "VCC_16") (pintype "power_in"))
    )
    (net (code "85") (name "unconnected-(U2-CTS#-Pad9)") (class "Default")
      (node (ref "U2") (pin "9") (pinfunction "CTS#_9") (pintype "passive+no_connect"))
    )
    (net (code "86") (name "unconnected-(U2-DCD#-Pad12)") (class "Default")
      (node (ref "U2") (pin "12") (pinfunction "DCD#_12") (pintype "passive+no_connect"))
    )
    (net (code "87") (name "unconnected-(U2-DSR#-Pad10)") (class "Default")
      (node (ref "U2") (pin "10") (pinfunction "DSR#_10") (pintype "passive+no_connect"))
    )
    (net (code "88") (name "unconnected-(U2-DTR#-Pad13)") (class "Default")
      (node (ref "U2") (pin "13") (pinfunction "DTR#_13") (pintype "passive+no_connect"))
    )
    (net (code "89") (name "unconnected-(U2-R232-Pad15)") (class "Default")
      (node (ref "U2") (pin "15") (pinfunction "R232_15") (pintype "passive+no_connect"))
    )
    (net (code "90") (name "unconnected-(U2-RI#-Pad11)") (class "Default")
      (node (ref "U2") (pin "11") (pinfunction "RI#_11") (pintype "passive+no_connect"))
    )
    (net (code "91") (name "unconnected-(U2-RTS#-Pad14)") (class "Default")
      (node (ref "U2") (pin "14") (pinfunction "RTS#_14") (pintype "passive+no_connect"))
    )
  )
)
